# food_dispenser.net
KiCad netlist of a schematic drawn in EAGLE
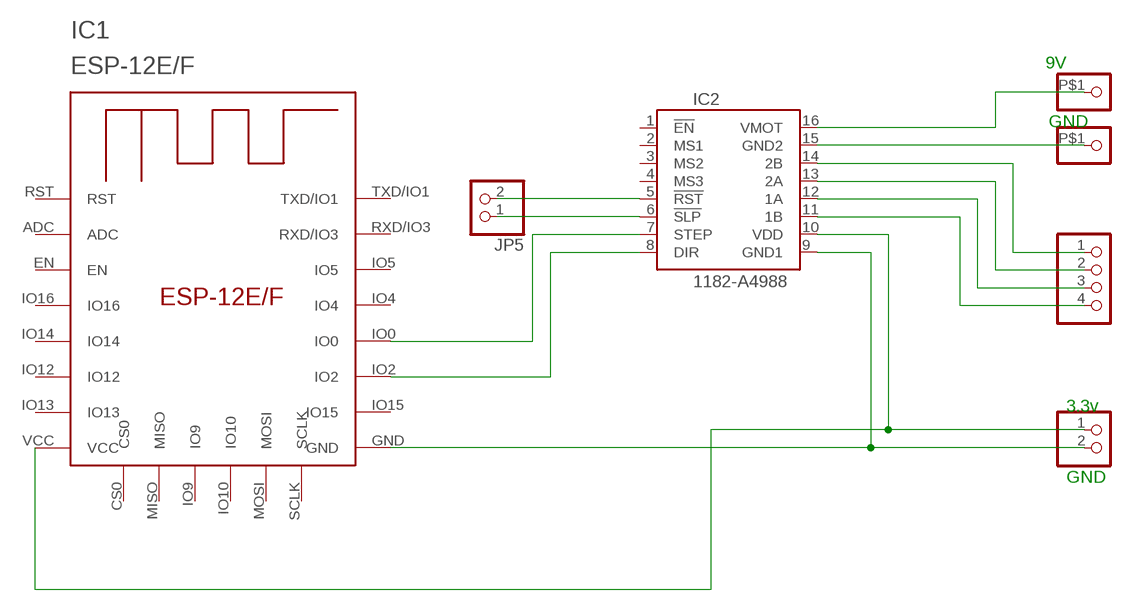
[diagram p0: schematic, sheet 1]

(export (version "E")
  (design (tool "Eeschema 10.0.6"))
  (components
    (comp (ref "IC1")
      (value "ESP-12E/F")
      (footprint "eagle-import:ESP-12E")
      (libsource (lib "eagle-import") (part "ESP-12E/F"))
    )
    (comp (ref "IC2")
      (value "1182-A4988")
      (footprint "eagle-import:A4988")
      (libsource (lib "eagle-import") (part "1182-A4988"))
    )
    (comp (ref "JP1")
      (value "PINHD-1X1-BIGPOGO")
      (footprint "eagle-import:1X1-BIGPOGO")
      (libsource (lib "eagle-import") (part "PINHD-1X1-BIGPOGO"))
    )
    (comp (ref "JP2")
      (value "PINHD-1X1-BIGPOGO")
      (footprint "eagle-import:1X1-BIGPOGO")
      (libsource (lib "eagle-import") (part "PINHD-1X1-BIGPOGO"))
    )
    (comp (ref "JP3")
      (value "PINHD-1X2")
      (footprint "eagle-import:1X02")
      (libsource (lib "eagle-import") (part "PINHD-1X2"))
    )
    (comp (ref "JP4")
      (value "PINHD-1X4")
      (footprint "eagle-import:1X04")
      (libsource (lib "eagle-import") (part "PINHD-1X4"))
    )
    (comp (ref "JP5")
      (value "PINHD-1X2")
      (footprint "eagle-import:1X02")
      (libsource (lib "eagle-import") (part "PINHD-1X2"))
    )
  )
  (nets
    (net (code "1") (name "Net-(IC2-1A)") (class "Default")
      (node (ref "IC2") (pin "12") (pinfunction "1A_12") (pintype "output"))
      (node (ref "JP4") (pin "3") (pinfunction "3_3") (pintype "passive"))
    )
    (net (code "2") (name "Net-(IC2-1B)") (class "Default")
      (node (ref "IC2") (pin "11") (pinfunction "1B_11") (pintype "output"))
      (node (ref "JP4") (pin "4") (pinfunction "4_4") (pintype "passive"))
    )
    (net (code "3") (name "Net-(IC2-2A)") (class "Default")
      (node (ref "IC2") (pin "13") (pinfunction "2A_13") (pintype "output"))
      (node (ref "JP4") (pin "2") (pinfunction "2_2") (pintype "passive"))
    )
    (net (code "4") (name "Net-(IC2-2B)") (class "Default")
      (node (ref "IC2") (pin "14") (pinfunction "2B_14") (pintype "output"))
      (node (ref "JP4") (pin "1") (pinfunction "1_1") (pintype "passive"))
    )
    (net (code "5") (name "Net-(IC2-DIR)") (class "Default")
      (node (ref "IC1") (pin "IO2") (pinfunction "IO2_IO2") (pintype "bidirectional"))
      (node (ref "IC2") (pin "8") (pinfunction "DIR_8") (pintype "input"))
    )
    (net (code "6") (name "Net-(IC2-GND1)") (class "Default")
      (node (ref "IC1") (pin "GND") (pinfunction "GND_GND") (pintype "power_in"))
      (node (ref "IC2") (pin "9") (pinfunction "GND1_9") (pintype "power_in"))
      (node (ref "JP3") (pin "2") (pinfunction "2_2") (pintype "passive"))
    )
    (net (code "7") (name "Net-(IC2-GND2)") (class "Default")
      (node (ref "IC2") (pin "15") (pinfunction "GND2_15") (pintype "power_in"))
      (node (ref "JP2") (pin "P$1") (pinfunction "1_P$1") (pintype "passive"))
    )
    (net (code "8") (name "Net-(IC2-STEP)") (class "Default")
      (node (ref "IC1") (pin "IO0") (pinfunction "IO0_IO0") (pintype "bidirectional"))
      (node (ref "IC2") (pin "7") (pinfunction "STEP_7") (pintype "input"))
    )
    (net (code "9") (name "Net-(IC2-VDD)") (class "Default")
      (node (ref "IC1") (pin "VCC") (pinfunction "VCC_VCC") (pintype "power_in"))
      (node (ref "IC2") (pin "10") (pinfunction "VDD_10") (pintype "power_in"))
      (node (ref "JP3") (pin "1") (pinfunction "1_1") (pintype "passive"))
    )
    (net (code "10") (name "Net-(IC2-VMOT)") (class "Default")
      (node (ref "IC2") (pin "16") (pinfunction "VMOT_16") (pintype "power_in"))
      (node (ref "JP1") (pin "P$1") (pinfunction "1_P$1") (pintype "passive"))
    )
    (net (code "11") (name "Net-(IC2-~{RST})") (class "Default")
      (node (ref "IC2") (pin "5") (pinfunction "~{RST}_5") (pintype "passive"))
      (node (ref "JP5") (pin "2") (pinfunction "2_2") (pintype "passive"))
    )
    (net (code "12") (name "Net-(IC2-~{SLP})") (class "Default")
      (node (ref "IC2") (pin "6") (pinfunction "~{SLP}_6") (pintype "passive"))
      (node (ref "JP5") (pin "1") (pinfunction "1_1") (pintype "passive"))
    )
    (net (code "13") (name "unconnected-(IC1-PadADC)") (class "Default")
      (node (ref "IC1") (pin "ADC") (pinfunction "ADC_ADC") (pintype "bidirectional"))
    )
    (net (code "14") (name "unconnected-(IC1-PadCS0)") (class "Default")
      (node (ref "IC1") (pin "CS0") (pinfunction "CS0_CS0") (pintype "bidirectional"))
    )
    (net (code "15") (name "unconnected-(IC1-PadEN)") (class "Default")
      (node (ref "IC1") (pin "EN") (pinfunction "EN_EN") (pintype "bidirectional"))
    )
    (net (code "16") (name "unconnected-(IC1-PadIO4)") (class "Default")
      (node (ref "IC1") (pin "IO4") (pinfunction "IO4_IO4") (pintype "bidirectional"))
    )
    (net (code "17") (name "unconnected-(IC1-PadIO5)") (class "Default")
      (node (ref "IC1") (pin "IO5") (pinfunction "IO5_IO5") (pintype "bidirectional"))
    )
    (net (code "18") (name "unconnected-(IC1-PadIO9)") (class "Default")
      (node (ref "IC1") (pin "IO9") (pinfunction "IO9_IO9") (pintype "bidirectional"))
    )
    (net (code "19") (name "unconnected-(IC1-PadIO10)") (class "Default")
      (node (ref "IC1") (pin "IO10") (pinfunction "IO10_IO10") (pintype "bidirectional"))
    )
    (net (code "20") (name "unconnected-(IC1-PadIO12)") (class "Default")
      (node (ref "IC1") (pin "IO12") (pinfunction "IO12_IO12") (pintype "bidirectional"))
    )
    (net (code "21") (name "unconnected-(IC1-PadIO13)") (class "Default")
      (node (ref "IC1") (pin "IO13") (pinfunction "IO13_IO13") (pintype "bidirectional"))
    )
    (net (code "22") (name "unconnected-(IC1-PadIO14)") (class "Default")
      (node (ref "IC1") (pin "IO14") (pinfunction "IO14_IO14") (pintype "bidirectional"))
    )
    (net (code "23") (name "unconnected-(IC1-PadIO15)") (class "Default")
      (node (ref "IC1") (pin "IO15") (pinfunction "IO15_IO15") (pintype "bidirectional"))
    )
    (net (code "24") (name "unconnected-(IC1-PadIO16)") (class "Default")
      (node (ref "IC1") (pin "IO16") (pinfunction "IO16_IO16") (pintype "bidirectional"))
    )
    (net (code "25") (name "unconnected-(IC1-PadMISO)") (class "Default")
      (node (ref "IC1") (pin "MISO") (pinfunction "MISO_MISO") (pintype "bidirectional"))
    )
    (net (code "26") (name "unconnected-(IC1-PadMOSI)") (class "Default")
      (node (ref "IC1") (pin "MOSI") (pinfunction "MOSI_MOSI") (pintype "bidirectional"))
    )
    (net (code "27") (name "unconnected-(IC1-PadRST)") (class "Default")
      (node (ref "IC1") (pin "RST") (pinfunction "RST_RST") (pintype "input"))
    )
    (net (code "28") (name "unconnected-(IC1-PadRXD{slash}IO3)") (class "Default")
      (node (ref "IC1") (pin "RXD/IO3") (pinfunction "RXD/IO3_RXD/IO3") (pintype "bidirectional"))
    )
    (net (code "29") (name "unconnected-(IC1-PadSCLK)") (class "Default")
      (node (ref "IC1") (pin "SCLK") (pinfunction "SCLK_SCLK") (pintype "bidirectional"))
    )
    (net (code "30") (name "unconnected-(IC1-PadTXD{slash}IO1)") (class "Default")
      (node (ref "IC1") (pin "TXD/IO1") (pinfunction "TXD/IO1_TXD/IO1") (pintype "bidirectional"))
    )
    (net (code "31") (name "unconnected-(IC2-MS1-Pad2)") (class "Default")
      (node (ref "IC2") (pin "2") (pinfunction "MS1_2") (pintype "passive"))
    )
    (net (code "32") (name "unconnected-(IC2-MS2-Pad3)") (class "Default")
      (node (ref "IC2") (pin "3") (pinfunction "MS2_3") (pintype "passive"))
    )
    (net (code "33") (name "unconnected-(IC2-MS3-Pad4)") (class "Default")
      (node (ref "IC2") (pin "4") (pinfunction "MS3_4") (pintype "passive"))
    )
    (net (code "34") (name "unconnected-(IC2-~{EN}-Pad1)") (class "Default")
      (node (ref "IC2") (pin "1") (pinfunction "~{EN}_1") (pintype "passive"))
    )
  )
)
